# programmer.net
KiCad netlist of a schematic drawn in EAGLE
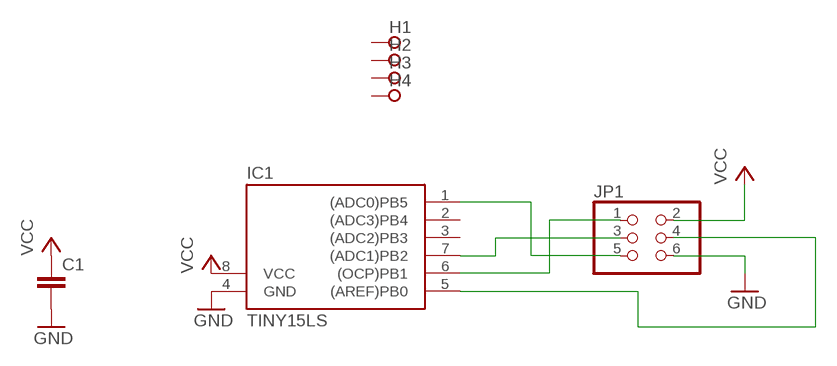
[diagram p0: schematic, sheet 1]

(export (version "E")
  (design (tool "Eeschema 10.0.6"))
  (components
    (comp (ref "C1")
      (value "C-EUC1206")
      (footprint "eagle-import:C1206")
      (libsource (lib "eagle-import") (part "C-EUC1206"))
    )
    (comp (ref "H1")
      (value "SPECIAL_DRILL_0.1000")
      (footprint "eagle-import:PAD_0.1000")
      (libsource (lib "eagle-import") (part "SPECIAL_DRILL_0.1000"))
    )
    (comp (ref "H2")
      (value "SPECIAL_DRILL_0.1000")
      (footprint "eagle-import:PAD_0.1000")
      (libsource (lib "eagle-import") (part "SPECIAL_DRILL_0.1000"))
    )
    (comp (ref "H3")
      (value "SPECIAL_DRILL_0.1000")
      (footprint "eagle-import:PAD_0.1000")
      (libsource (lib "eagle-import") (part "SPECIAL_DRILL_0.1000"))
    )
    (comp (ref "H4")
      (value "SPECIAL_DRILL_0.1000")
      (footprint "eagle-import:PAD_0.1000")
      (libsource (lib "eagle-import") (part "SPECIAL_DRILL_0.1000"))
    )
    (comp (ref "IC1")
      (value "TINY15LS")
      (footprint "eagle-import:SOIC8")
      (libsource (lib "eagle-import") (part "TINY15LS"))
    )
    (comp (ref "JP1")
      (value "PINHD-2X3")
      (footprint "eagle-import:2X03")
      (libsource (lib "eagle-import") (part "PINHD-2X3"))
    )
  )
  (nets
    (net (code "1") (name "GND") (class "Default")
      (node (ref "C1") (pin "2") (pinfunction "2_2") (pintype "passive"))
      (node (ref "IC1") (pin "4") (pinfunction "GND_4") (pintype "power_in"))
      (node (ref "JP1") (pin "6") (pinfunction "6_6") (pintype "passive"))
    )
    (net (code "2") (name "Net-(IC1-(ADC0)PB5)") (class "Default")
      (node (ref "IC1") (pin "1") (pinfunction "(ADC0)PB5_1") (pintype "bidirectional"))
      (node (ref "JP1") (pin "5") (pinfunction "5_5") (pintype "passive"))
    )
    (net (code "3") (name "Net-(IC1-(ADC1)PB2)") (class "Default")
      (node (ref "IC1") (pin "7") (pinfunction "(ADC1)PB2_7") (pintype "bidirectional"))
      (node (ref "JP1") (pin "3") (pinfunction "3_3") (pintype "passive"))
    )
    (net (code "4") (name "Net-(IC1-(AREF)PB0)") (class "Default")
      (node (ref "IC1") (pin "5") (pinfunction "(AREF)PB0_5") (pintype "bidirectional"))
      (node (ref "JP1") (pin "4") (pinfunction "4_4") (pintype "passive"))
    )
    (net (code "5") (name "Net-(IC1-(OCP)PB1)") (class "Default")
      (node (ref "IC1") (pin "6") (pinfunction "(OCP)PB1_6") (pintype "bidirectional"))
      (node (ref "JP1") (pin "1") (pinfunction "1_1") (pintype "passive"))
    )
    (net (code "6") (name "VCC") (class "Default")
      (node (ref "C1") (pin "1") (pinfunction "1_1") (pintype "passive"))
      (node (ref "IC1") (pin "8") (pinfunction "VCC_8") (pintype "power_in"))
      (node (ref "JP1") (pin "2") (pinfunction "2_2") (pintype "passive"))
    )
    (net (code "7") (name "unconnected-(H1-Pad1)") (class "Default")
      (node (ref "H1") (pin "1") (pinfunction "1_1") (pintype "passive"))
    )
    (net (code "8") (name "unconnected-(H2-Pad1)") (class "Default")
      (node (ref "H2") (pin "1") (pinfunction "1_1") (pintype "passive"))
    )
    (net (code "9") (name "unconnected-(H3-Pad1)") (class "Default")
      (node (ref "H3") (pin "1") (pinfunction "1_1") (pintype "passive"))
    )
    (net (code "10") (name "unconnected-(H4-Pad1)") (class "Default")
      (node (ref "H4") (pin "1") (pinfunction "1_1") (pintype "passive"))
    )
    (net (code "11") (name "unconnected-(IC1-(ADC2)PB3-Pad3)") (class "Default")
      (node (ref "IC1") (pin "3") (pinfunction "(ADC2)PB3_3") (pintype "bidirectional"))
    )
    (net (code "12") (name "unconnected-(IC1-(ADC3)PB4-Pad2)") (class "Default")
      (node (ref "IC1") (pin "2") (pinfunction "(ADC3)PB4_2") (pintype "bidirectional"))
    )
  )
)
